# logic.net
KiCad netlist of a schematic drawn in EAGLE
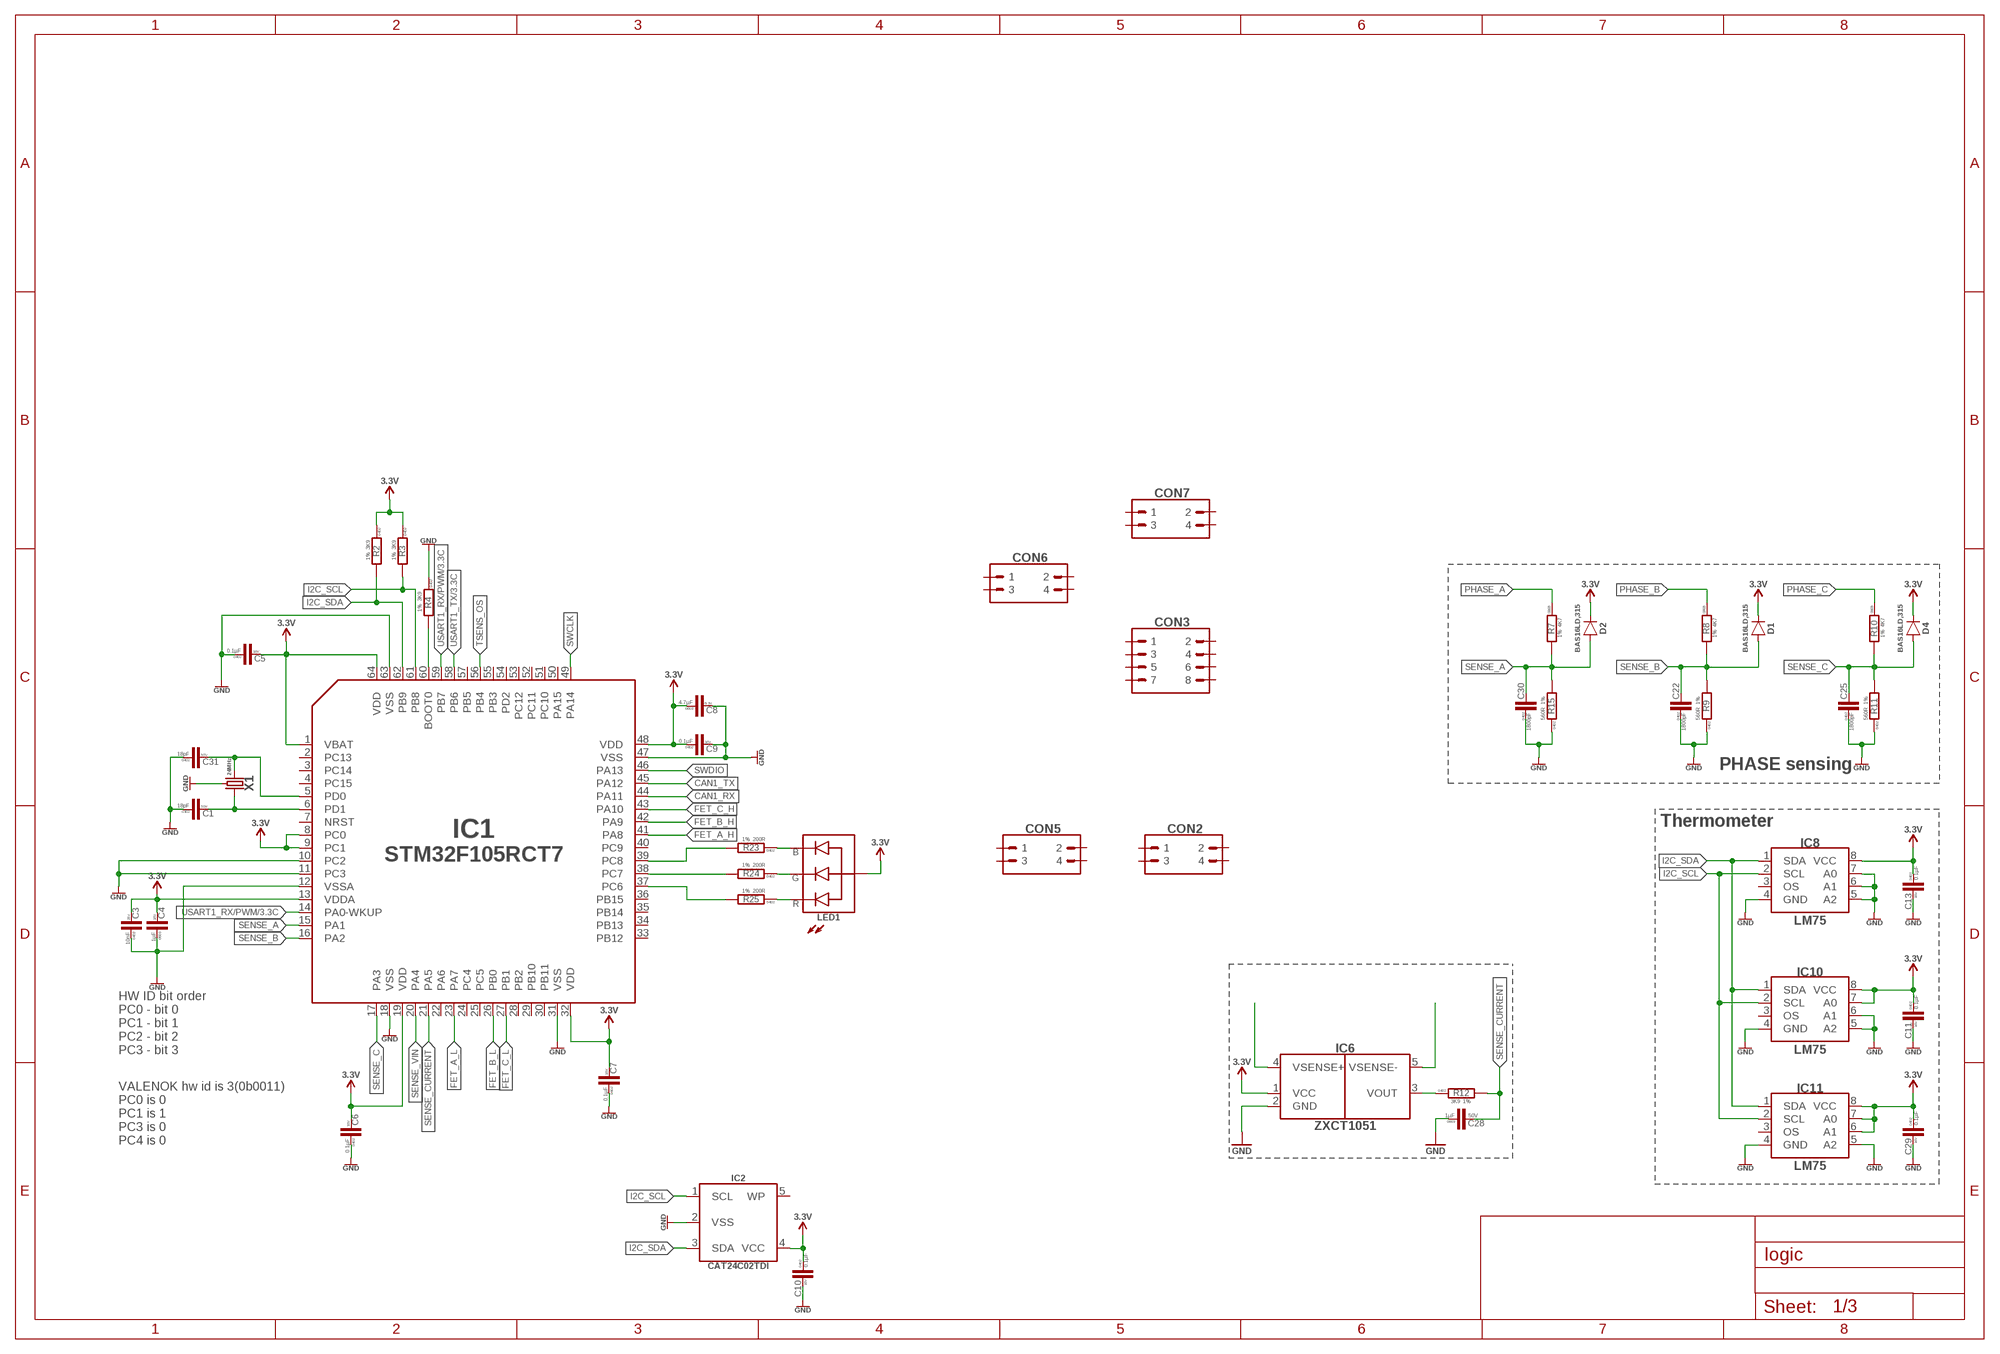
[diagram p0: schematic, sheet 1]
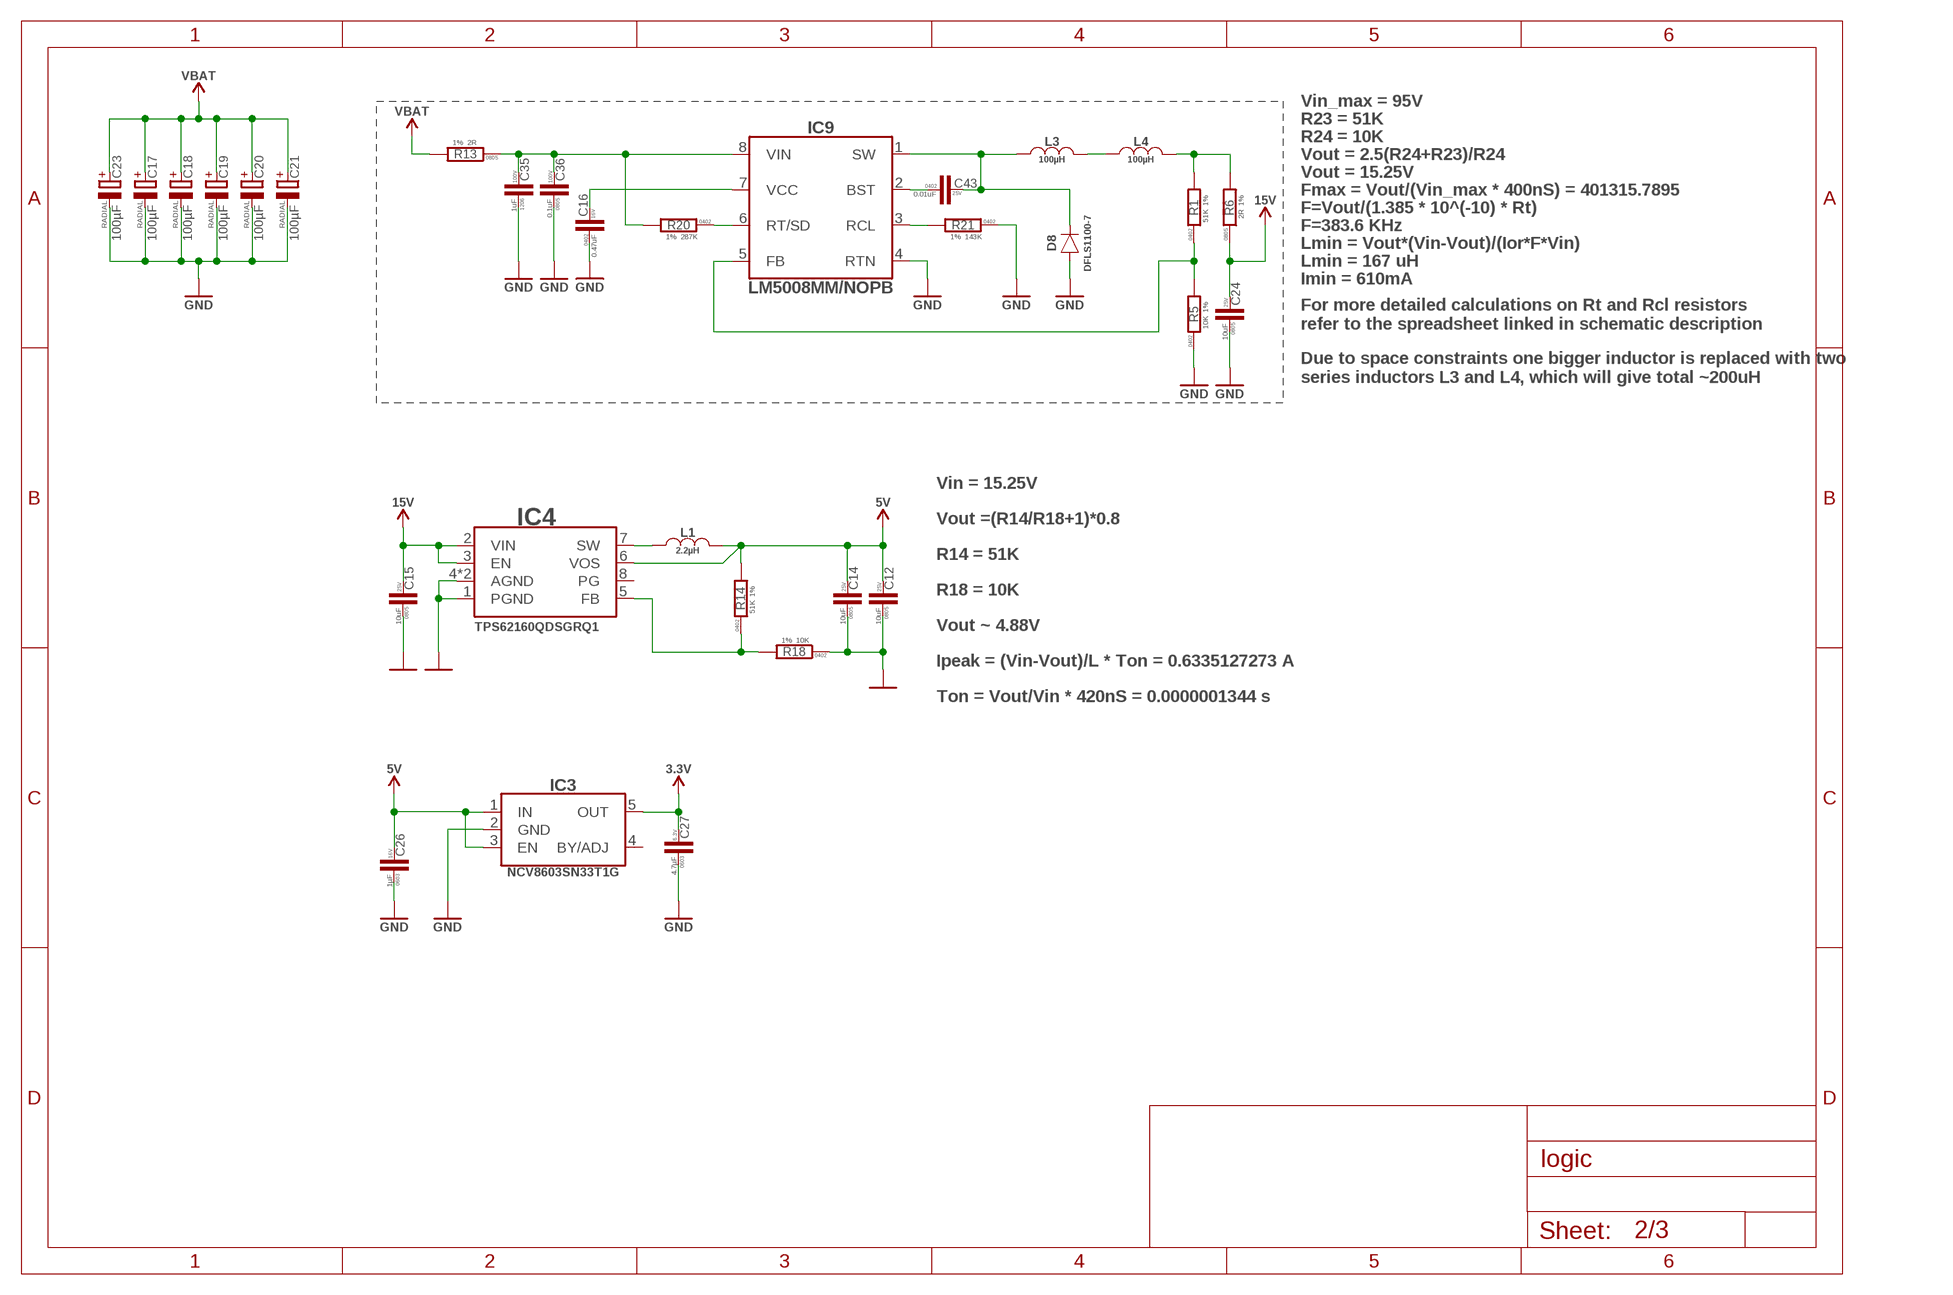
[diagram p1: schematic, sheet 2]
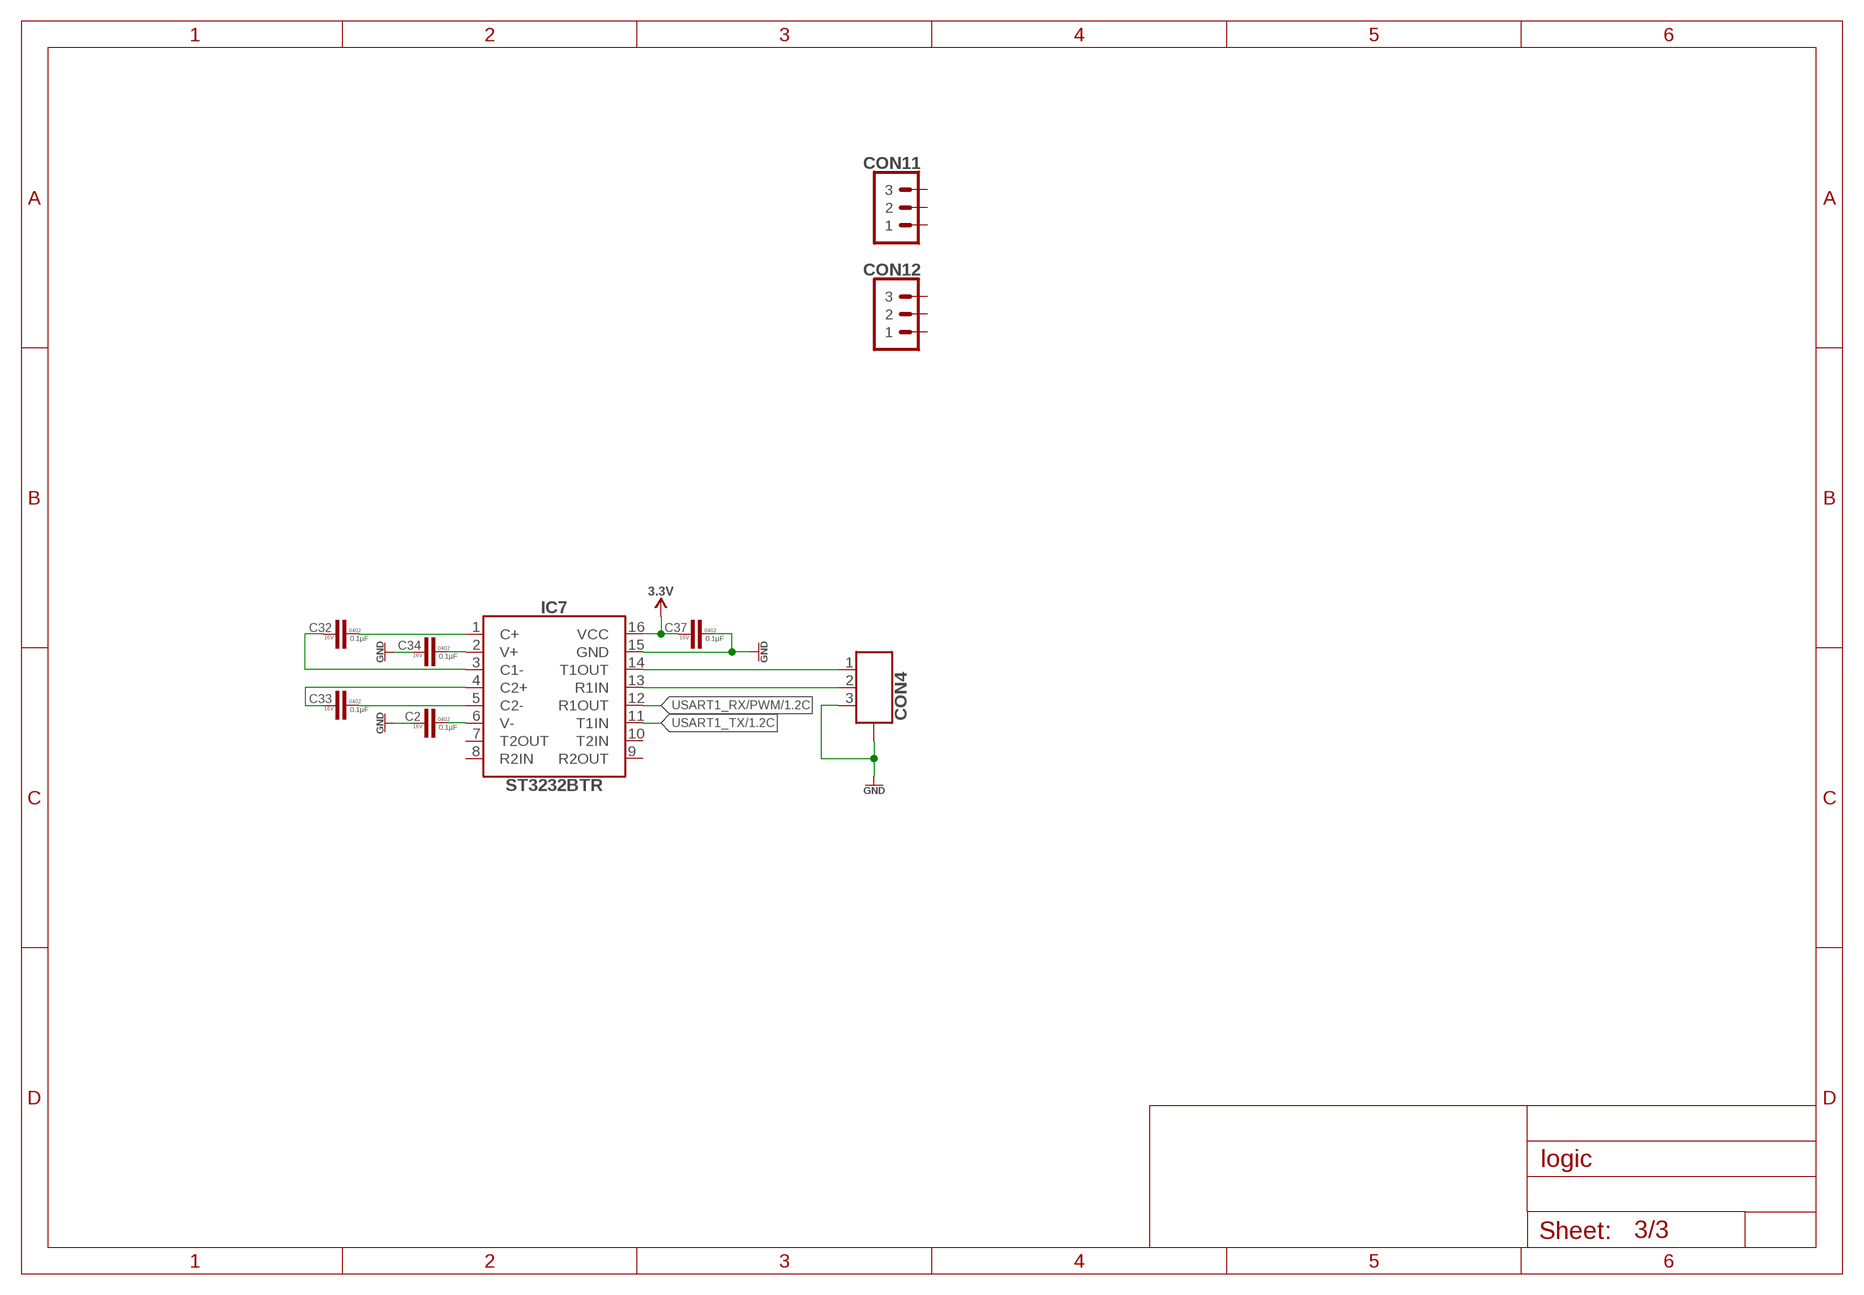
[diagram p2: schematic, sheet 3]

(export (version "E")
  (design (tool "Eeschema 10.0.6"))
  (components
    (comp (ref "C1")
      (value "18pF")
      (footprint "eagle-import:C0402")
      (fields
        (field (name "PACKAGE") "0402")
        (field (name "AEC-Q") "---")
        (field (name "DIGIKEY#") "399-8828-1-ND")
        (field (name "MANF") "Kemet")
        (field (name "MANF#") "CBR04C180F5GAC")
        (field (name "OPERATING_TEMP") "-55°C ~ 125°C")
        (field (name "VOLTAGE") "50V")
      )
      (libsource (lib "eagle-import") (part "C-0402"))
    )
    (comp (ref "C3")
      (value "10nF")
      (footprint "eagle-import:C0402")
      (fields
        (field (name "PACKAGE") "0402")
        (field (name "AEC-Q") "---")
        (field (name "DIGIKEY#") "490-6043-1-ND")
        (field (name "MANF") "Murata Electronics")
        (field (name "MANF#") "GCM155R71E103KA37D")
        (field (name "OPERATING_TEMP") "-55°C ~ 125°C")
        (field (name "VOLTAGE") "25V")
      )
      (libsource (lib "eagle-import") (part "C-0402"))
    )
    (comp (ref "C4")
      (value "1µF")
      (footprint "eagle-import:C0603")
      (fields
        (field (name "PACKAGE") "0603")
        (field (name "AEC-Q") "AEC-Q200")
        (field (name "DIGIKEY#") "445-12539-1-ND")
        (field (name "MANF") "TDK Corporation")
        (field (name "MANF#") "CGA3E1X7R1C105K080AC")
        (field (name "OPERATING_TEMP") "-55°C ~ 125°C")
        (field (name "VOLTAGE") "16V")
      )
      (libsource (lib "eagle-import") (part "C-0603"))
    )
    (comp (ref "C5")
      (value "0.1µF")
      (footprint "eagle-import:C0402")
      (fields
        (field (name "PACKAGE") "0402")
        (field (name "AEC-Q") "---")
        (field (name "DIGIKEY#") "490-3261-1-ND")
        (field (name "MANF") "Murata Electronics")
        (field (name "MANF#") "GRM155R71C104KA88D")
        (field (name "OPERATING_TEMP") "-55°C ~ 125°C")
        (field (name "VOLTAGE") "16V")
      )
      (libsource (lib "eagle-import") (part "C-0402"))
    )
    (comp (ref "C6")
      (value "0.1µF")
      (footprint "eagle-import:C0402")
      (fields
        (field (name "PACKAGE") "0402")
        (field (name "AEC-Q") "---")
        (field (name "DIGIKEY#") "490-3261-1-ND")
        (field (name "MANF") "Murata Electronics")
        (field (name "MANF#") "GRM155R71C104KA88D")
        (field (name "OPERATING_TEMP") "-55°C ~ 125°C")
        (field (name "VOLTAGE") "16V")
      )
      (libsource (lib "eagle-import") (part "C-0402"))
    )
    (comp (ref "C7")
      (value "0.1µF")
      (footprint "eagle-import:C0402")
      (fields
        (field (name "PACKAGE") "0402")
        (field (name "AEC-Q") "---")
        (field (name "DIGIKEY#") "490-3261-1-ND")
        (field (name "MANF") "Murata Electronics")
        (field (name "MANF#") "GRM155R71C104KA88D")
        (field (name "OPERATING_TEMP") "-55°C ~ 125°C")
        (field (name "VOLTAGE") "16V")
      )
      (libsource (lib "eagle-import") (part "C-0402"))
    )
    (comp (ref "C8")
      (value "4.7µF")
      (footprint "eagle-import:C0603")
      (fields
        (field (name "PACKAGE") "0603")
        (field (name "AEC-Q") "---")
        (field (name "MANF") "Samsung Electro-Mechanics")
        (field (name "MANF#") "CL10B475KQ8NQNC")
        (field (name "OPERATING_TEMP") "-55°C ~ 125°C")
        (field (name "VOLTAGE") "6.3V")
      )
      (libsource (lib "eagle-import") (part "C-0603"))
    )
    (comp (ref "C9")
      (value "0.1µF")
      (footprint "eagle-import:C0402")
      (fields
        (field (name "PACKAGE") "0402")
        (field (name "AEC-Q") "---")
        (field (name "DIGIKEY#") "490-3261-1-ND")
        (field (name "MANF") "Murata Electronics")
        (field (name "MANF#") "GRM155R71C104KA88D")
        (field (name "OPERATING_TEMP") "-55°C ~ 125°C")
        (field (name "VOLTAGE") "16V")
      )
      (libsource (lib "eagle-import") (part "C-0402"))
    )
    (comp (ref "C10")
      (value "0.1µF")
      (footprint "eagle-import:C0402")
      (fields
        (field (name "PACKAGE") "0402")
        (field (name "AEC-Q") "---")
        (field (name "DIGIKEY#") "490-3261-1-ND")
        (field (name "MANF") "Murata Electronics")
        (field (name "MANF#") "GRM155R71C104KA88D")
        (field (name "OPERATING_TEMP") "-55°C ~ 125°C")
        (field (name "VOLTAGE") "16V")
      )
      (libsource (lib "eagle-import") (part "C-0402"))
    )
    (comp (ref "C11")
      (value "0.1µF")
      (footprint "eagle-import:C0402")
      (fields
        (field (name "PACKAGE") "0402")
        (field (name "AEC-Q") "---")
        (field (name "DIGIKEY#") "490-3261-1-ND")
        (field (name "MANF") "Murata Electronics")
        (field (name "MANF#") "GRM155R71C104KA88D")
        (field (name "OPERATING_TEMP") "-55°C ~ 125°C")
        (field (name "VOLTAGE") "16V")
      )
      (libsource (lib "eagle-import") (part "C-0402"))
    )
    (comp (ref "C13")
      (value "0.1µF")
      (footprint "eagle-import:C0402")
      (fields
        (field (name "PACKAGE") "0402")
        (field (name "AEC-Q") "---")
        (field (name "DIGIKEY#") "490-3261-1-ND")
        (field (name "MANF") "Murata Electronics")
        (field (name "MANF#") "GRM155R71C104KA88D")
        (field (name "OPERATING_TEMP") "-55°C ~ 125°C")
        (field (name "VOLTAGE") "16V")
      )
      (libsource (lib "eagle-import") (part "C-0402"))
    )
    (comp (ref "C22")
      (value "1800pF")
      (footprint "eagle-import:C0402")
      (fields (field (name "PACKAGE") "0402"))
      (libsource (lib "eagle-import") (part "C-0402"))
    )
    (comp (ref "C25")
      (value "1800pF")
      (footprint "eagle-import:C0402")
      (fields (field (name "PACKAGE") "0402"))
      (libsource (lib "eagle-import") (part "C-0402"))
    )
    (comp (ref "C28")
      (value "1µF")
      (footprint "eagle-import:C0603")
      (fields
        (field (name "MANF") "Taiyo Yuden")
        (field (name "PACKAGE") "0603")
        (field (name "TOLERANCE") "+-10%")
        (field (name "VOLTAGE") "50V")
      )
      (libsource (lib "eagle-import") (part "1µF-0603-50V_10%_X7R"))
    )
    (comp (ref "C29")
      (value "0.1µF")
      (footprint "eagle-import:C0402")
      (fields
        (field (name "PACKAGE") "0402")
        (field (name "AEC-Q") "---")
        (field (name "DIGIKEY#") "490-3261-1-ND")
        (field (name "MANF") "Murata Electronics")
        (field (name "MANF#") "GRM155R71C104KA88D")
        (field (name "OPERATING_TEMP") "-55°C ~ 125°C")
        (field (name "VOLTAGE") "16V")
      )
      (libsource (lib "eagle-import") (part "C-0402"))
    )
    (comp (ref "C30")
      (value "1800pF")
      (footprint "eagle-import:C0402")
      (fields (field (name "PACKAGE") "0402"))
      (libsource (lib "eagle-import") (part "C-0402"))
    )
    (comp (ref "C31")
      (value "18pF")
      (footprint "eagle-import:C0402")
      (fields
        (field (name "PACKAGE") "0402")
        (field (name "AEC-Q") "---")
        (field (name "DIGIKEY#") "399-8828-1-ND")
        (field (name "MANF") "Kemet")
        (field (name "MANF#") "CBR04C180F5GAC")
        (field (name "OPERATING_TEMP") "-55°C ~ 125°C")
        (field (name "VOLTAGE") "50V")
      )
      (libsource (lib "eagle-import") (part "C-0402"))
    )
    (comp (ref "CON2")
      (value "PINHEAD_2X02-PTH-2-MALE")
      (footprint "eagle-import:2X02-PTH-2")
      (libsource (lib "eagle-import") (part "PINHEAD_2X02-PTH-2-MALE"))
    )
    (comp (ref "CON3")
      (value "PINHEAD_2X04-PLS-2")
      (footprint "eagle-import:2X04-PTH-2")
      (libsource (lib "eagle-import") (part "PINHEAD_2X04-PLS-2"))
    )
    (comp (ref "CON5")
      (value "PINHEAD_2X02-PTH-2-MALE")
      (footprint "eagle-import:2X02-PTH-2")
      (libsource (lib "eagle-import") (part "PINHEAD_2X02-PTH-2-MALE"))
    )
    (comp (ref "CON6")
      (value "PINHEAD_2X02-PTH-2-MALE")
      (footprint "eagle-import:2X02-PTH-2")
      (libsource (lib "eagle-import") (part "PINHEAD_2X02-PTH-2-MALE"))
    )
    (comp (ref "CON7")
      (value "PINHEAD_2X02-PTH-2-MALE")
      (footprint "eagle-import:2X02-PTH-2")
      (libsource (lib "eagle-import") (part "PINHEAD_2X02-PTH-2-MALE"))
    )
    (comp (ref "D1")
      (value "BAS16L")
      (footprint "eagle-import:SOD882")
      (fields (field (name "MANF#") "BAS16LD,315") (field (name "MANF") "Nexperia USA Inc"))
      (libsource (lib "eagle-import") (part "BAS16L"))
    )
    (comp (ref "D2")
      (value "BAS16L")
      (footprint "eagle-import:SOD882")
      (fields (field (name "MANF#") "BAS16LD,315") (field (name "MANF") "Nexperia USA Inc"))
      (libsource (lib "eagle-import") (part "BAS16L"))
    )
    (comp (ref "D4")
      (value "BAS16L")
      (footprint "eagle-import:SOD882")
      (fields (field (name "MANF#") "BAS16LD,315") (field (name "MANF") "Nexperia USA Inc"))
      (libsource (lib "eagle-import") (part "BAS16L"))
    )
    (comp (ref "IC1")
      (value "STM32F105RCT6")
      (footprint "eagle-import:TQFP64")
      (fields
        (field (name "MANF#") "STM32F105RCT6")
        (field (name "MANF") "STMicroelectronics")
        (field (name "DIGIKEY#") "497-11547-ND")
        (field (name "MANF#_1") "STM32F105RCT7")
      )
      (libsource (lib "eagle-import") (part "STM32F105RCT6"))
    )
    (comp (ref "IC2")
      (value "CAT24C02")
      (footprint "eagle-import:SOT23-5L@1")
      (fields (field (name "MANF") "ON Semiconductor"))
      (libsource (lib "eagle-import") (part "CAT24C02"))
    )
    (comp (ref "IC6")
      (value "ZXCT1051")
      (footprint "eagle-import:SOT23-5L")
      (fields (field (name "MANF") "Diodes Incorporated"))
      (libsource (lib "eagle-import") (part "ZXCT1051"))
    )
    (comp (ref "IC8")
      (value "LM75-TSSOP8")
      (footprint "eagle-import:TSSOP8")
      (fields (field (name "MANF") "NXP Semiconductors"))
      (libsource (lib "eagle-import") (part "LM75-TSSOP8"))
    )
    (comp (ref "IC10")
      (value "LM75-TSSOP8")
      (footprint "eagle-import:TSSOP8")
      (fields (field (name "MANF") "NXP Semiconductors"))
      (libsource (lib "eagle-import") (part "LM75-TSSOP8"))
    )
    (comp (ref "IC11")
      (value "LM75-TSSOP8")
      (footprint "eagle-import:TSSOP8")
      (fields (field (name "MANF") "NXP Semiconductors"))
      (libsource (lib "eagle-import") (part "LM75-TSSOP8"))
    )
    (comp (ref "LED1")
      (value "LTST-C19HE1WT")
      (footprint "eagle-import:0606")
      (fields (field (name "MANF") "Lite-On Inc"))
      (libsource (lib "eagle-import") (part "LTST-C19HE1WT"))
    )
    (comp (ref "R2")
      (value "3K9")
      (footprint "eagle-import:R0402")
      (fields
        (field (name "PACKAGE") "0402")
        (field (name "TOLERANCE") "1%")
        (field (name "AEC-Q") "---")
        (field (name "DIGIKEY#") "311-3.90KLRCT-ND")
        (field (name "MANF") "Yageo")
        (field (name "MANF#") "RC0402FR-073K9L")
        (field (name "OPERATING_TEMP") "-55°C ~ 155°C")
      )
      (libsource (lib "eagle-import") (part "R-0402-1%"))
    )
    (comp (ref "R3")
      (value "3K9")
      (footprint "eagle-import:R0402")
      (fields
        (field (name "PACKAGE") "0402")
        (field (name "TOLERANCE") "1%")
        (field (name "AEC-Q") "---")
        (field (name "DIGIKEY#") "311-3.90KLRCT-ND")
        (field (name "MANF") "Yageo")
        (field (name "MANF#") "RC0402FR-073K9L")
        (field (name "OPERATING_TEMP") "-55°C ~ 155°C")
      )
      (libsource (lib "eagle-import") (part "R-0402-1%"))
    )
    (comp (ref "R4")
      (value "3K9")
      (footprint "eagle-import:R0402")
      (fields
        (field (name "PACKAGE") "0402")
        (field (name "TOLERANCE") "1%")
        (field (name "AEC-Q") "---")
        (field (name "DIGIKEY#") "311-3.90KLRCT-ND")
        (field (name "MANF") "Yageo")
        (field (name "MANF#") "RC0402FR-073K9L")
        (field (name "OPERATING_TEMP") "-55°C ~ 155°C")
      )
      (libsource (lib "eagle-import") (part "R-0402-1%"))
    )
    (comp (ref "R7")
      (value "4K7")
      (footprint "eagle-import:R0805")
      (fields (field (name "PACKAGE") "0805") (field (name "TOLERANCE") "1%"))
      (libsource (lib "eagle-import") (part "R-0805-1%"))
    )
    (comp (ref "R8")
      (value "4K7")
      (footprint "eagle-import:R0805")
      (fields (field (name "PACKAGE") "0805") (field (name "TOLERANCE") "1%"))
      (libsource (lib "eagle-import") (part "R-0805-1%"))
    )
    (comp (ref "R9")
      (value "560R")
      (footprint "eagle-import:R0402")
      (fields (field (name "PACKAGE") "0402") (field (name "TOLERANCE") "1%"))
      (libsource (lib "eagle-import") (part "R-0402-1%"))
    )
    (comp (ref "R10")
      (value "4K7")
      (footprint "eagle-import:R0805")
      (fields (field (name "PACKAGE") "0805") (field (name "TOLERANCE") "1%"))
      (libsource (lib "eagle-import") (part "R-0805-1%"))
    )
    (comp (ref "R11")
      (value "560R")
      (footprint "eagle-import:R0402")
      (fields (field (name "PACKAGE") "0402") (field (name "TOLERANCE") "1%"))
      (libsource (lib "eagle-import") (part "R-0402-1%"))
    )
    (comp (ref "R12")
      (value "3K9")
      (footprint "eagle-import:R0402")
      (fields (field (name "MANF") "Yageo") (field (name "PACKAGE") "0402") (field (name "TOLERANCE") "1%"))
      (libsource (lib "eagle-import") (part "3K9-0402-1%"))
    )
    (comp (ref "R15")
      (value "560R")
      (footprint "eagle-import:R0402")
      (fields (field (name "PACKAGE") "0402") (field (name "TOLERANCE") "1%"))
      (libsource (lib "eagle-import") (part "R-0402-1%"))
    )
    (comp (ref "R23")
      (value "200R")
      (footprint "eagle-import:R0402")
      (fields
        (field (name "PACKAGE") "0402")
        (field (name "TOLERANCE") "1%")
        (field (name "AEC-Q") "---")
        (field (name "DIGIKEY#") "311-200JRCT-ND")
        (field (name "MANF") "Yageo")
        (field (name "MANF#") "RC0402JR-07200RL")
        (field (name "OPERATING_TEMP") "-55°C ~ 155°C")
      )
      (libsource (lib "eagle-import") (part "R-0402-1%"))
    )
    (comp (ref "R24")
      (value "200R")
      (footprint "eagle-import:R0402")
      (fields
        (field (name "PACKAGE") "0402")
        (field (name "TOLERANCE") "1%")
        (field (name "AEC-Q") "---")
        (field (name "DIGIKEY#") "311-200JRCT-ND")
        (field (name "MANF") "Yageo")
        (field (name "MANF#") "RC0402JR-07200RL")
        (field (name "OPERATING_TEMP") "-55°C ~ 155°C")
      )
      (libsource (lib "eagle-import") (part "R-0402-1%"))
    )
    (comp (ref "R25")
      (value "200R")
      (footprint "eagle-import:R0402")
      (fields
        (field (name "PACKAGE") "0402")
        (field (name "TOLERANCE") "1%")
        (field (name "AEC-Q") "---")
        (field (name "DIGIKEY#") "311-200JRCT-ND")
        (field (name "MANF") "Yageo")
        (field (name "MANF#") "RC0402JR-07200RL")
        (field (name "OPERATING_TEMP") "-55°C ~ 155°C")
      )
      (libsource (lib "eagle-import") (part "R-0402-1%"))
    )
    (comp (ref "X1")
      (value "24MHz")
      (footprint "eagle-import:OSCILLATOR-3.2X2.5-4P")
      (fields
        (field (name "MANF") "Kyocera International Inc. Electronic Components")
        (field (name "DIGIKEY#") "1253-1198-1-ND")
        (field (name "MANF#") "CX3225GB24000P0HPQCC")
      )
      (libsource (lib "eagle-import") (part "CRYSTAL-4P-3.2X2.5-4P-24MHZ"))
    )
    (comp (ref "C12")
      (value "10uF")
      (footprint "eagle-import:C0805")
      (fields
        (field (name "PACKAGE") "0805")
        (field (name "AEC-Q") "AEC-Q200")
        (field (name "DIGIKEY#") "445-181411-1-ND")
        (field (name "MANF") "TDK Corporation")
        (field (name "MANF#") "CGA4J1X7S1E106K125AE")
        (field (name "VOLTAGE") "25V")
      )
      (libsource (lib "eagle-import") (part "C-0805"))
    )
    (comp (ref "C14")
      (value "10uF")
      (footprint "eagle-import:C0805")
      (fields
        (field (name "PACKAGE") "0805")
        (field (name "AEC-Q") "AEC-Q200")
        (field (name "DIGIKEY#") "445-181411-1-ND")
        (field (name "MANF") "TDK Corporation")
        (field (name "MANF#") "CGA4J1X7S1E106K125AE")
        (field (name "VOLTAGE") "25V")
      )
      (libsource (lib "eagle-import") (part "C-0805"))
    )
    (comp (ref "C15")
      (value "10uF")
      (footprint "eagle-import:C0805")
      (fields
        (field (name "PACKAGE") "0805")
        (field (name "AEC-Q") "AEC-Q200")
        (field (name "DIGIKEY#") "445-181411-1-ND")
        (field (name "MANF") "TDK Corporation")
        (field (name "MANF#") "CGA4J1X7S1E106K125AE")
        (field (name "VOLTAGE") "25V")
      )
      (libsource (lib "eagle-import") (part "C-0805"))
    )
    (comp (ref "C16")
      (value "0.47uF")
      (footprint "eagle-import:C0402")
      (fields
        (field (name "PACKAGE") "0402")
        (field (name "AEC-Q") "AEC-Q200")
        (field (name "DIGIKEY#") "490-12244-1-ND")
        (field (name "MANF") "Murata Electronics")
        (field (name "MANF#") "GRT155C81C474ME01D")
        (field (name "VOLTAGE") "16V")
      )
      (libsource (lib "eagle-import") (part "C-0402"))
    )
    (comp (ref "C17")
      (value "100µF")
      (footprint "eagle-import:RADIAL_SIDE_12.5X22")
      (fields
        (field (name "PACKAGE") "RADIAL")
        (field (name "MANF") "EPCOS (TDK)")
        (field (name "VOLTAGE") "50V")
        (field (name "DIGIKEY#") "493-4784-3-ND")
        (field (name "MANF_1") "Nichicon")
        (field (name "MANF#") "UCY2C101MHD1TO")
        (field (name "VOLTAGE_1") "160V")
      )
      (libsource (lib "eagle-import") (part "CPOL-RADIAL_SIDE-12.5-22"))
    )
    (comp (ref "C18")
      (value "100µF")
      (footprint "eagle-import:RADIAL_SIDE_12.5X22")
      (fields
        (field (name "PACKAGE") "RADIAL")
        (field (name "MANF") "EPCOS (TDK)")
        (field (name "VOLTAGE") "50V")
        (field (name "DIGIKEY#") "493-4784-3-ND")
        (field (name "MANF_1") "Nichicon")
        (field (name "MANF#") "UCY2C101MHD1TO")
        (field (name "VOLTAGE_1") "160V")
      )
      (libsource (lib "eagle-import") (part "CPOL-RADIAL_SIDE-12.5-22"))
    )
    (comp (ref "C19")
      (value "100µF")
      (footprint "eagle-import:RADIAL_SIDE_12.5X22")
      (fields
        (field (name "PACKAGE") "RADIAL")
        (field (name "MANF") "EPCOS (TDK)")
        (field (name "VOLTAGE") "50V")
        (field (name "DIGIKEY#") "493-4784-3-ND")
        (field (name "MANF_1") "Nichicon")
        (field (name "MANF#") "UCY2C101MHD1TO")
        (field (name "VOLTAGE_1") "160V")
      )
      (libsource (lib "eagle-import") (part "CPOL-RADIAL_SIDE-12.5-22"))
    )
    (comp (ref "C20")
      (value "100µF")
      (footprint "eagle-import:RADIAL_SIDE_12.5X22")
      (fields
        (field (name "PACKAGE") "RADIAL")
        (field (name "MANF") "EPCOS (TDK)")
        (field (name "VOLTAGE") "50V")
        (field (name "DIGIKEY#") "493-4784-3-ND")
        (field (name "MANF_1") "Nichicon")
        (field (name "MANF#") "UCY2C101MHD1TO")
        (field (name "VOLTAGE_1") "160V")
      )
      (libsource (lib "eagle-import") (part "CPOL-RADIAL_SIDE-12.5-22"))
    )
    (comp (ref "C21")
      (value "100µF")
      (footprint "eagle-import:RADIAL_SIDE_12.5X22")
      (fields
        (field (name "PACKAGE") "RADIAL")
        (field (name "MANF") "EPCOS (TDK)")
        (field (name "VOLTAGE") "50V")
        (field (name "DIGIKEY#") "493-4784-3-ND")
        (field (name "MANF_1") "Nichicon")
        (field (name "MANF#") "UCY2C101MHD1TO")
        (field (name "VOLTAGE_1") "160V")
      )
      (libsource (lib "eagle-import") (part "CPOL-RADIAL_SIDE-12.5-22"))
    )
    (comp (ref "C23")
      (value "100µF")
      (footprint "eagle-import:RADIAL_SIDE_12.5X22")
      (fields
        (field (name "PACKAGE") "RADIAL")
        (field (name "MANF") "EPCOS (TDK)")
        (field (name "VOLTAGE") "50V")
        (field (name "DIGIKEY#") "493-4784-3-ND")
        (field (name "MANF_1") "Nichicon")
        (field (name "MANF#") "UCY2C101MHD1TO")
        (field (name "VOLTAGE_1") "160V")
      )
      (libsource (lib "eagle-import") (part "CPOL-RADIAL_SIDE-12.5-22"))
    )
    (comp (ref "C24")
      (value "10uF")
      (footprint "eagle-import:C0805")
      (fields
        (field (name "PACKAGE") "0805")
        (field (name "AEC-Q") "AEC-Q200")
        (field (name "DIGIKEY#") "445-181411-1-ND")
        (field (name "MANF") "TDK Corporation")
        (field (name "MANF#") "CGA4J1X7S1E106K125AE")
        (field (name "VOLTAGE") "25V")
      )
      (libsource (lib "eagle-import") (part "C-0805"))
    )
    (comp (ref "C26")
      (value "1µF")
      (footprint "eagle-import:C0603")
      (fields
        (field (name "PACKAGE") "0603")
        (field (name "AEC-Q") "AEC-Q200")
        (field (name "DIGIKEY#") "445-12539-1-ND")
        (field (name "MANF") "TDK Corporation")
        (field (name "MANF#") "CGA3E1X7R1C105K080AC")
        (field (name "OPERATING_TEMP") "-55°C ~ 125°C")
        (field (name "VOLTAGE") "16V")
      )
      (libsource (lib "eagle-import") (part "C-0603"))
    )
    (comp (ref "C27")
      (value "4.7µF")
      (footprint "eagle-import:C0603")
      (fields
        (field (name "PACKAGE") "0603")
        (field (name "AEC-Q") "---")
        (field (name "DIGIKEY#") "1276-2087-1-ND")
        (field (name "MANF") "Samsung Electro-Mechanics")
        (field (name "MANF#") "CL10B475KQ8NQNC")
        (field (name "OPERATING_TEMP") "-55°C ~ 125°C")
        (field (name "VOLTAGE") "6.3V")
      )
      (libsource (lib "eagle-import") (part "C-0603"))
    )
    (comp (ref "C35")
      (value "1uF")
      (footprint "eagle-import:C1206")
      (fields
        (field (name "PACKAGE") "1206")
        (field (name "AEC-Q") "AEC-Q200")
        (field (name "DIGIKEY#") "490-16468-1-ND")
        (field (name "MANF") "Murata Electronics")
        (field (name "MANF#") "GCJ31CR72A105KA01L")
        (field (name "VOLTAGE") "100V")
      )
      (libsource (lib "eagle-import") (part "C-1206"))
    )
    (comp (ref "C36")
      (value "0.1uF")
      (footprint "eagle-import:C0805")
      (fields
        (field (name "PACKAGE") "0805")
        (field (name "AEC-Q") "AEC-Q200")
        (field (name "DIGIKEY#") "445-5827-1-ND")
        (field (name "MANF") "TDK Corporation")
        (field (name "MANF#") "CGA4J2X7R2A104K125AA")
        (field (name "VOLTAGE") "100V")
      )
      (libsource (lib "eagle-import") (part "C-0805"))
    )
    (comp (ref "C43")
      (value "0.01uF")
      (footprint "eagle-import:C0402")
      (fields
        (field (name "PACKAGE") "0402")
        (field (name "DIGIKEY#") "490-6043-1-ND")
        (field (name "MANF") "Murata Electronics")
        (field (name "MANF#") "GCM155R71E103KA37D")
        (field (name "VOLTAGE") "25V")
      )
      (libsource (lib "eagle-import") (part "C-0402"))
    )
    (comp (ref "D8")
      (value "DFLS1100")
      (footprint "eagle-import:POWERDI-123")
      (fields (field (name "MANF#") "DFLS1100-7") (field (name "MANF") "Diodes Incorporated"))
      (libsource (lib "eagle-import") (part "DFLS1100"))
    )
    (comp (ref "IC3")
      (value "NCV8603SN33")
      (footprint "eagle-import:SOT23-5")
      (fields (field (name "MANF") "ON Semiconductor") (field (name "MANF#") "NCV8603SN33T1G"))
      (libsource (lib "eagle-import") (part "NCV8603SN33"))
    )
    (comp (ref "IC4")
      (value "TPS62160QDSGRQ1")
      (footprint "eagle-import:WFDFN-8")
      (fields
        (field (name "MANF#") "TPS62160DSGR")
        (field (name "MANF") "Texas Instruments")
        (field (name "AEC-Q") "AEC-Q100")
        (field (name "DIGIKEY#") "296-40840-1-ND")
        (field (name "MANF#_1") "TPS62160QDSGRQ1")
      )
      (libsource (lib "eagle-import") (part "TPS62160QDSGRQ1"))
    )
    (comp (ref "IC9")
      (value "LM5008-MSOP8")
      (footprint "eagle-import:MSOP8")
      (fields (field (name "MANF#") "LM5008MM/NOPB") (field (name "MANF") "Texas Instruments"))
      (libsource (lib "eagle-import") (part "LM5008-MSOP8"))
    )
    (comp (ref "L1")
      (value "2.2µH")
      (footprint "eagle-import:NR3015")
      (fields (field (name "MANF") "Taiyo Yuden"))
      (libsource (lib "eagle-import") (part "2.2µH-NRS3015"))
    )
    (comp (ref "L3")
      (value "100µH")
      (footprint "eagle-import:LQS-6028")
      (fields (field (name "MANF") "Wurth Electronics Inc"))
      (libsource (lib "eagle-import") (part "100µH-LQS-6028"))
    )
    (comp (ref "L4")
      (value "100µH")
      (footprint "eagle-import:LQS-6028")
      (fields (field (name "MANF") "Wurth Electronics Inc"))
      (libsource (lib "eagle-import") (part "100µH-LQS-6028"))
    )
    (comp (ref "R1")
      (value "51K")
      (footprint "eagle-import:R0402")
      (fields
        (field (name "PACKAGE") "0402")
        (field (name "TOLERANCE") "1%")
        (field (name "AEC-Q") "AEC-Q200")
        (field (name "DIGIKEY#") "P51.0KLCT-ND")
        (field (name "MANF") "Panasonic Electronic Components")
        (field (name "MANF#") "ERJ-2RKF5102X")
      )
      (libsource (lib "eagle-import") (part "R-0402-1%"))
    )
    (comp (ref "R5")
      (value "10K")
      (footprint "eagle-import:R0402")
      (fields
        (field (name "PACKAGE") "0402")
        (field (name "TOLERANCE") "1%")
        (field (name "AEC-Q") "AEC-Q200")
        (field (name "DIGIKEY#") "P10.0KLCT-ND")
        (field (name "MANF") "Panasonic Electronic Components")
        (field (name "MANF#") "ERJ-2RKF1002X")
      )
      (libsource (lib "eagle-import") (part "R-0402-1%"))
    )
    (comp (ref "R6")
      (value "2R")
      (footprint "eagle-import:R0805")
      (fields
        (field (name "PACKAGE") "0805")
        (field (name "TOLERANCE") "1%")
        (field (name "DIGIKEY#") "RMCF0805FT2R00CT-ND")
        (field (name "MANF") "Stackpole Electronics Inc")
        (field (name "MANF#") "RMCF0805FT2R00")
      )
      (libsource (lib "eagle-import") (part "R-0805-1%"))
    )
    (comp (ref "R13")
      (value "2R")
      (footprint "eagle-import:R0805")
      (fields
        (field (name "PACKAGE") "0805")
        (field (name "TOLERANCE") "1%")
        (field (name "DIGIKEY#") "RMCF0805FT2R00CT-ND")
        (field (name "MANF") "Stackpole Electronics Inc")
        (field (name "MANF#") "RMCF0805FT2R00")
      )
      (libsource (lib "eagle-import") (part "R-0805-1%"))
    )
    (comp (ref "R14")
      (value "51K")
      (footprint "eagle-import:R0402")
      (fields
        (field (name "PACKAGE") "0402")
        (field (name "TOLERANCE") "1%")
        (field (name "AEC-Q") "AEC-Q200")
        (field (name "DIGIKEY#") "P51.0KLCT-ND")
        (field (name "MANF") "Panasonic Electronic Components")
        (field (name "MANF#") "ERJ-2RKF5102X")
      )
      (libsource (lib "eagle-import") (part "R-0402-1%"))
    )
    (comp (ref "R18")
      (value "10K")
      (footprint "eagle-import:R0402")
      (fields
        (field (name "PACKAGE") "0402")
        (field (name "TOLERANCE") "1%")
        (field (name "AEC-Q") "AEC-Q200")
        (field (name "DIGIKEY#") "P10.0KLCT-ND")
        (field (name "MANF") "Panasonic Electronic Components")
        (field (name "MANF#") "ERJ-2RKF1002X")
      )
      (libsource (lib "eagle-import") (part "R-0402-1%"))
    )
    (comp (ref "R20")
      (value "287K")
      (footprint "eagle-import:R0402")
      (fields
        (field (name "PACKAGE") "0402")
        (field (name "TOLERANCE") "1%")
        (field (name "AEC-Q") "AEC-Q200")
        (field (name "DIGIKEY#") "P287KLCT-ND")
        (field (name "MANF") "Panasonic Electronic Components")
        (field (name "MANF#") "ERJ-2RKF2873X")
      )
      (libsource (lib "eagle-import") (part "R-0402-1%"))
    )
    (comp (ref "R21")
      (value "143K")
      (footprint "eagle-import:R0402")
      (fields
        (field (name "PACKAGE") "0402")
        (field (name "TOLERANCE") "1%")
        (field (name "AEC-Q") "AEC-Q200")
        (field (name "DIGIKEY#") "P122734CT-ND")
        (field (name "MANF") "Panasonic Electronic Components")
        (field (name "MANF#") "ERJ-1GNF1433C")
      )
      (libsource (lib "eagle-import") (part "R-0402-1%"))
    )
    (comp (ref "C2")
      (value "0.1µF")
      (footprint "eagle-import:C0402")
      (fields
        (field (name "PACKAGE") "0402")
        (field (name "AEC-Q") "---")
        (field (name "DIGIKEY#") "490-3261-1-ND")
        (field (name "MANF") "Murata Electronics")
        (field (name "MANF#") "GRM155R71C104KA88D")
        (field (name "OPERATING_TEMP") "-55°C ~ 125°C")
        (field (name "VOLTAGE") "16V")
      )
      (libsource (lib "eagle-import") (part "C-0402"))
    )
    (comp (ref "C32")
      (value "0.1µF")
      (footprint "eagle-import:C0402")
      (fields
        (field (name "PACKAGE") "0402")
        (field (name "AEC-Q") "---")
        (field (name "DIGIKEY#") "490-3261-1-ND")
        (field (name "MANF") "Murata Electronics")
        (field (name "MANF#") "GRM155R71C104KA88D")
        (field (name "OPERATING_TEMP") "-55°C ~ 125°C")
        (field (name "VOLTAGE") "16V")
      )
      (libsource (lib "eagle-import") (part "C-0402"))
    )
    (comp (ref "C33")
      (value "0.1µF")
      (footprint "eagle-import:C0402")
      (fields
        (field (name "PACKAGE") "0402")
        (field (name "AEC-Q") "---")
        (field (name "DIGIKEY#") "490-3261-1-ND")
        (field (name "MANF") "Murata Electronics")
        (field (name "MANF#") "GRM155R71C104KA88D")
        (field (name "OPERATING_TEMP") "-55°C ~ 125°C")
        (field (name "VOLTAGE") "16V")
      )
      (libsource (lib "eagle-import") (part "C-0402"))
    )
    (comp (ref "C34")
      (value "0.1µF")
      (footprint "eagle-import:C0402")
      (fields
        (field (name "PACKAGE") "0402")
        (field (name "AEC-Q") "---")
        (field (name "DIGIKEY#") "490-3261-1-ND")
        (field (name "MANF") "Murata Electronics")
        (field (name "MANF#") "GRM155R71C104KA88D")
        (field (name "OPERATING_TEMP") "-55°C ~ 125°C")
        (field (name "VOLTAGE") "16V")
      )
      (libsource (lib "eagle-import") (part "C-0402"))
    )
    (comp (ref "C37")
      (value "0.1µF")
      (footprint "eagle-import:C0402")
      (fields
        (field (name "PACKAGE") "0402")
        (field (name "AEC-Q") "---")
        (field (name "DIGIKEY#") "490-3261-1-ND")
        (field (name "MANF") "Murata Electronics")
        (field (name "MANF#") "GRM155R71C104KA88D")
        (field (name "OPERATING_TEMP") "-55°C ~ 125°C")
        (field (name "VOLTAGE") "16V")
      )
      (libsource (lib "eagle-import") (part "C-0402"))
    )
    (comp (ref "CON4")
      (value "CON-3P-TABS")
      (footprint "eagle-import:JST_GH-3P-RA")
      (libsource (lib "eagle-import") (part "CON-3P-TABS"))
    )
    (comp (ref "CON11")
      (value "PINHEAD_1X03-2")
      (footprint "eagle-import:1X03-PTH-2")
      (libsource (lib "eagle-import") (part "PINHEAD_1X03-2"))
    )
    (comp (ref "CON12")
      (value "PINHEAD_1X03-2")
      (footprint "eagle-import:1X03-PTH-2")
      (libsource (lib "eagle-import") (part "PINHEAD_1X03-2"))
    )
    (comp (ref "IC7")
      (value "ST3232")
      (footprint "eagle-import:TSSOP16")
      (fields (field (name "MANF#") "ST3232BTR") (field (name "MANF") "STMicroelectronics"))
      (libsource (lib "eagle-import") (part "ST3232"))
    )
  )
  (nets
    (net (code "1") (name "CAN1_RX") (class "Default")
      (node (ref "IC1") (pin "44") (pinfunction "PA11_44") (pintype "bidirectional"))
    )
    (net (code "2") (name "CAN1_TX") (class "Default")
      (node (ref "IC1") (pin "45") (pinfunction "PA12_45") (pintype "bidirectional"))
    )
    (net (code "3") (name "FET_A_H") (class "Default")
      (node (ref "IC1") (pin "41") (pinfunction "PA8_41") (pintype "bidirectional"))
    )
    (net (code "4") (name "FET_A_L") (class "Default")
      (node (ref "IC1") (pin "23") (pinfunction "PA7_23") (pintype "bidirectional"))
    )
    (net (code "5") (name "FET_B_H") (class "Default")
      (node (ref "IC1") (pin "42") (pinfunction "PA9_42") (pintype "bidirectional"))
    )
    (net (code "6") (name "FET_B_L") (class "Default")
      (node (ref "IC1") (pin "26") (pinfunction "PB0_26") (pintype "bidirectional"))
    )
    (net (code "7") (name "FET_C_H") (class "Default")
      (node (ref "IC1") (pin "43") (pinfunction "PA10_43") (pintype "bidirectional"))
    )
    (net (code "8") (name "FET_C_L") (class "Default")
      (node (ref "IC1") (pin "27") (pinfunction "PB1_27") (pintype "bidirectional"))
    )
    (net (code "9") (name "GND") (class "Default")
      (node (ref "C1") (pin "1") (pinfunction "1_1") (pintype "passive"))
      (node (ref "C10") (pin "2") (pinfunction "2_2") (pintype "passive"))
      (node (ref "C11") (pin "2") (pinfunction "2_2") (pintype "passive"))
      (node (ref "C12") (pin "1") (pinfunction "1_1") (pintype "passive"))
      (node (ref "C13") (pin "2") (pinfunction "2_2") (pintype "passive"))
      (node (ref "C14") (pin "1") (pinfunction "1_1") (pintype "passive"))
      (node (ref "C15") (pin "1") (pinfunction "1_1") (pintype "passive"))
      (node (ref "C16") (pin "1") (pinfunction "1_1") (pintype "passive"))
      (node (ref "C17") (pin "-") (pinfunction "-_-") (pintype "passive"))
      (node (ref "C18") (pin "-") (pinfunction "-_-") (pintype "passive"))
      (node (ref "C19") (pin "-") (pinfunction "-_-") (pintype "passive"))
      (node (ref "C2") (pin "2") (pinfunction "2_2") (pintype "passive"))
      (node (ref "C20") (pin "-") (pinfunction "-_-") (pintype "passive"))
      (node (ref "C21") (pin "-") (pinfunction "-_-") (pintype "passive"))
      (node (ref "C22") (pin "1") (pinfunction "1_1") (pintype "passive"))
      (node (ref "C23") (pin "-") (pinfunction "-_-") (pintype "passive"))
      (node (ref "C24") (pin "1") (pinfunction "1_1") (pintype "passive"))
      (node (ref "C25") (pin "1") (pinfunction "1_1") (pintype "passive"))
      (node (ref "C26") (pin "1") (pinfunction "1_1") (pintype "passive"))
      (node (ref "C27") (pin "1") (pinfunction "1_1") (pintype "passive"))
      (node (ref "C28") (pin "P$1") (pinfunction "1_P$1") (pintype "passive"))
      (node (ref "C29") (pin "2") (pinfunction "2_2") (pintype "passive"))
      (node (ref "C3") (pin "1") (pinfunction "1_1") (pintype "passive"))
      (node (ref "C30") (pin "1") (pinfunction "1_1") (pintype "passive"))
      (node (ref "C31") (pin "1") (pinfunction "1_1") (pintype "passive"))
      (node (ref "C34") (pin "2") (pinfunction "2_2") (pintype "passive"))
      (node (ref "C35") (pin "P$1") (pinfunction "1_P$1") (pintype "passive"))
      (node (ref "C36") (pin "1") (pinfunction "1_1") (pintype "passive"))
      (node (ref "C37") (pin "1") (pinfunction "1_1") (pintype "passive"))
      (node (ref "C4") (pin "1") (pinfunction "1_1") (pintype "passive"))
      (node (ref "C5") (pin "1") (pinfunction "1_1") (pintype "passive"))
      (node (ref "C6") (pin "1") (pinfunction "1_1") (pintype "passive"))
      (node (ref "C7") (pin "1") (pinfunction "1_1") (pintype "passive"))
      (node (ref "C8") (pin "2") (pinfunction "2_2") (pintype "passive"))
      (node (ref "C9") (pin "2") (pinfunction "2_2") (pintype "passive"))
      (node (ref "CON4") (pin "3") (pinfunction "3_3") (pintype "bidirectional"))
      (node (ref "CON4") (pin "M$0") (pinfunction "GND_M$0") (pintype "bidirectional"))
      (node (ref "CON4") (pin "M$1") (pinfunction "GND_M$1") (pintype "bidirectional"))
      (node (ref "D8") (pin "A") (pinfunction "A_A") (pintype "passive"))
      (node (ref "IC1") (pin "10") (pinfunction "PC2_10") (pintype "bidirectional"))
      (node (ref "IC1") (pin "11") (pinfunction "PC3_11") (pintype "bidirectional"))
      (node (ref "IC1") (pin "12") (pinfunction "VSSA_12") (pintype "bidirectional"))
      (node (ref "IC1") (pin "18") (pinfunction "VSS_18") (pintype "bidirectional"))
      (node (ref "IC1") (pin "31") (pinfunction "VSS_31") (pintype "bidirectional"))
      (node (ref "IC1") (pin "47") (pinfunction "VSS_47") (pintype "bidirectional"))
      (node (ref "IC1") (pin "63") (pinfunction "VSS_63") (pintype "bidirectional"))
      (node (ref "IC10") (pin "4") (pinfunction "GND_4") (pintype "bidirectional"))
      (node (ref "IC10") (pin "5") (pinfunction "A2_5") (pintype "bidirectional"))
      (node (ref "IC10") (pin "6") (pinfunction "A1_6") (pintype "bidirectional"))
      (node (ref "IC11") (pin "4") (pinfunction "GND_4") (pintype "bidirectional"))
      (node (ref "IC11") (pin "5") (pinfunction "A2_5") (pintype "bidirectional"))
      (node (ref "IC2") (pin "2") (pinfunction "VSS_2") (pintype "bidirectional"))
      (node (ref "IC3") (pin "2") (pinfunction "GND_2") (pintype "power_in"))
      (node (ref "IC4") (pin "1") (pinfunction "PGND_1") (pintype "bidirectional"))
      (node (ref "IC4") (pin "4") (pinfunction "AGND_4") (pintype "bidirectional"))
      (node (ref "IC4") (pin "EP") (pinfunction "AGND_EP") (pintype "bidirectional"))
      (node (ref "IC6") (pin "2") (pinfunction "GND_2") (pintype "bidirectional"))
      (node (ref "IC7") (pin "15") (pinfunction "GND_15") (pintype "bidirectional"))
      (node (ref "IC8") (pin "4") (pinfunction "GND_4") (pintype "bidirectional"))
      (node (ref "IC8") (pin "5") (pinfunction "A2_5") (pintype "bidirectional"))
      (node (ref "IC8") (pin "6") (pinfunction "A1_6") (pintype "bidirectional"))
      (node (ref "IC8") (pin "7") (pinfunction "A0_7") (pintype "bidirectional"))
      (node (ref "IC9") (pin "4") (pinfunction "RTN_4") (pintype "bidirectional"))
      (node (ref "R11") (pin "1") (pinfunction "1_1") (pintype "passive"))
      (node (ref "R15") (pin "1") (pinfunction "1_1") (pintype "passive"))
      (node (ref "R18") (pin "1") (pinfunction "1_1") (pintype "passive"))
      (node (ref "R21") (pin "1") (pinfunction "1_1") (pintype "passive"))
      (node (ref "R4") (pin "1") (pinfunction "1_1") (pintype "passive"))
      (node (ref "R5") (pin "1") (pinfunction "1_1") (pintype "passive"))
      (node (ref "R9") (pin "1") (pinfunction "1_1") (pintype "passive"))
      (node (ref "X1") (pin "2") (pinfunction "GND_2") (pintype "bidirectional"))
      (node (ref "X1") (pin "4") (pinfunction "GND_4") (pintype "bidirectional"))
    )
    (net (code "10") (name "I2C_SCL") (class "Default")
      (node (ref "IC1") (pin "61") (pinfunction "PB8_61") (pintype "bidirectional"))
      (node (ref "IC10") (pin "2") (pinfunction "SCL_2") (pintype "bidirectional"))
      (node (ref "IC11") (pin "2") (pinfunction "SCL_2") (pintype "bidirectional"))
      (node (ref "IC2") (pin "1") (pinfunction "SCL_1") (pintype "bidirectional"))
      (node (ref "IC8") (pin "2") (pinfunction "SCL_2") (pintype "bidirectional"))
      (node (ref "R3") (pin "2") (pinfunction "2_2") (pintype "passive"))
    )
    (net (code "11") (name "I2C_SDA") (class "Default")
      (node (ref "IC1") (pin "62") (pinfunction "PB9_62") (pintype "bidirectional"))
      (node (ref "IC10") (pin "1") (pinfunction "SDA_1") (pintype "bidirectional"))
      (node (ref "IC11") (pin "1") (pinfunction "SDA_1") (pintype "bidirectional"))
      (node (ref "IC2") (pin "3") (pinfunction "SDA_3") (pintype "bidirectional"))
      (node (ref "IC8") (pin "1") (pinfunction "SDA_1") (pintype "bidirectional"))
      (node (ref "R2") (pin "2") (pinfunction "2_2") (pintype "passive"))
    )
    (net (code "12") (name "Net-(C35-2)") (class "Default")
      (node (ref "C35") (pin "P$2") (pinfunction "2_P$2") (pintype "passive"))
      (node (ref "C36") (pin "2") (pinfunction "2_2") (pintype "passive"))
      (node (ref "IC9") (pin "8") (pinfunction "VIN_8") (pintype "bidirectional"))
      (node (ref "R13") (pin "1") (pinfunction "1_1") (pintype "passive"))
      (node (ref "R20") (pin "2") (pinfunction "2_2") (pintype "passive"))
    )
    (net (code "13") (name "Net-(IC1-BOOT0)") (class "Default")
      (node (ref "IC1") (pin "60") (pinfunction "BOOT0_60") (pintype "bidirectional"))
      (node (ref "R4") (pin "2") (pinfunction "2_2") (pintype "passive"))
    )
    (net (code "14") (name "Net-(IC1-PC6)") (class "Default")
      (node (ref "IC1") (pin "37") (pinfunction "PC6_37") (pintype "bidirectional"))
      (node (ref "R25") (pin "2") (pinfunction "2_2") (pintype "passive"))
    )
    (net (code "15") (name "Net-(IC1-PC7)") (class "Default")
      (node (ref "IC1") (pin "38") (pinfunction "PC7_38") (pintype "bidirectional"))
      (node (ref "R24") (pin "2") (pinfunction "2_2") (pintype "passive"))
    )
    (net (code "16") (name "Net-(IC1-PC8)") (class "Default")
      (node (ref "IC1") (pin "39") (pinfunction "PC8_39") (pintype "bidirectional"))
      (node (ref "R23") (pin "2") (pinfunction "2_2") (pintype "passive"))
    )
    (net (code "17") (name "Net-(IC1-PD0)") (class "Default")
      (node (ref "C31") (pin "2") (pinfunction "2_2") (pintype "passive"))
      (node (ref "IC1") (pin "5") (pinfunction "PD0_5") (pintype "bidirectional"))
      (node (ref "X1") (pin "3") (pinfunction "2_3") (pintype "passive"))
    )
    (net (code "18") (name "Net-(IC1-PD1)") (class "Default")
      (node (ref "C1") (pin "2") (pinfunction "2_2") (pintype "passive"))
      (node (ref "IC1") (pin "6") (pinfunction "PD1_6") (pintype "bidirectional"))
      (node (ref "X1") (pin "1") (pinfunction "1_1") (pintype "passive"))
    )
    (net (code "19") (name "Net-(IC4-FB)") (class "Default")
      (node (ref "IC4") (pin "5") (pinfunction "FB_5") (pintype "bidirectional"))
      (node (ref "R14") (pin "1") (pinfunction "1_1") (pintype "passive"))
      (node (ref "R18") (pin "2") (pinfunction "2_2") (pintype "passive"))
    )
    (net (code "20") (name "Net-(IC4-SW)") (class "Default")
      (node (ref "IC4") (pin "7") (pinfunction "SW_7") (pintype "bidirectional"))
      (node (ref "L1") (pin "1") (pinfunction "1_1") (pintype "bidirectional"))
    )
    (net (code "21") (name "Net-(IC6-VOUT)") (class "Default")
      (node (ref "IC6") (pin "3") (pinfunction "VOUT_3") (pintype "bidirectional"))
      (node (ref "R12") (pin "1") (pinfunction "1_1") (pintype "passive"))
    )
    (net (code "22") (name "Net-(IC7-C+)") (class "Default")
      (node (ref "C32") (pin "1") (pinfunction "1_1") (pintype "passive"))
      (node (ref "IC7") (pin "1") (pinfunction "C+_1") (pintype "bidirectional"))
    )
    (net (code "23") (name "Net-(IC7-C1-)") (class "Default")
      (node (ref "C32") (pin "2") (pinfunction "2_2") (pintype "passive"))
      (node (ref "IC7") (pin "3") (pinfunction "C1-_3") (pintype "bidirectional"))
    )
    (net (code "24") (name "Net-(IC7-C2+)") (class "Default")
      (node (ref "C33") (pin "2") (pinfunction "2_2") (pintype "passive"))
      (node (ref "IC7") (pin "4") (pinfunction "C2+_4") (pintype "bidirectional"))
    )
    (net (code "25") (name "Net-(IC7-C2-)") (class "Default")
      (node (ref "C33") (pin "1") (pinfunction "1_1") (pintype "passive"))
      (node (ref "IC7") (pin "5") (pinfunction "C2-_5") (pintype "bidirectional"))
    )
    (net (code "26") (name "Net-(IC7-R1IN)") (class "Default")
      (node (ref "CON4") (pin "2") (pinfunction "2_2") (pintype "bidirectional"))
      (node (ref "IC7") (pin "13") (pinfunction "R1IN_13") (pintype "bidirectional"))
    )
    (net (code "27") (name "Net-(IC7-T1OUT)") (class "Default")
      (node (ref "CON4") (pin "1") (pinfunction "1_1") (pintype "bidirectional"))
      (node (ref "IC7") (pin "14") (pinfunction "T1OUT_14") (pintype "bidirectional"))
    )
    (net (code "28") (name "Net-(IC7-V+)") (class "Default")
      (node (ref "C34") (pin "1") (pinfunction "1_1") (pintype "passive"))
      (node (ref "IC7") (pin "2") (pinfunction "V+_2") (pintype "bidirectional"))
    )
    (net (code "29") (name "Net-(IC7-V-)") (class "Default")
      (node (ref "C2") (pin "1") (pinfunction "1_1") (pintype "passive"))
      (node (ref "IC7") (pin "6") (pinfunction "V-_6") (pintype "bidirectional"))
    )
    (net (code "30") (name "Net-(IC9-BST)") (class "Default")
      (node (ref "C43") (pin "1") (pinfunction "1_1") (pintype "passive"))
      (node (ref "IC9") (pin "2") (pinfunction "BST_2") (pintype "bidirectional"))
    )
    (net (code "31") (name "Net-(IC9-FB)") (class "Default")
      (node (ref "IC9") (pin "5") (pinfunction "FB_5") (pintype "bidirectional"))
      (node (ref "R1") (pin "1") (pinfunction "1_1") (pintype "passive"))
      (node (ref "R5") (pin "2") (pinfunction "2_2") (pintype "passive"))
    )
    (net (code "32") (name "Net-(IC9-RCL)") (class "Default")
      (node (ref "IC9") (pin "3") (pinfunction "RCL_3") (pintype "bidirectional"))
      (node (ref "R21") (pin "2") (pinfunction "2_2") (pintype "passive"))
    )
    (net (code "33") (name "Net-(IC9-RT{slash}SD)") (class "Default")
      (node (ref "IC9") (pin "6") (pinfunction "RT/SD_6") (pintype "bidirectional"))
      (node (ref "R20") (pin "1") (pinfunction "1_1") (pintype "passive"))
    )
    (net (code "34") (name "Net-(IC9-SW)") (class "Default")
      (node (ref "C43") (pin "2") (pinfunction "2_2") (pintype "passive"))
      (node (ref "D8") (pin "C") (pinfunction "C_C") (pintype "passive"))
      (node (ref "IC9") (pin "1") (pinfunction "SW_1") (pintype "bidirectional"))
      (node (ref "L3") (pin "P$1") (pinfunction "1_P$1") (pintype "bidirectional"))
    )
    (net (code "35") (name "Net-(IC9-VCC)") (class "Default")
      (node (ref "C16") (pin "2") (pinfunction "2_2") (pintype "passive"))
      (node (ref "IC9") (pin "7") (pinfunction "VCC_7") (pintype "bidirectional"))
    )
    (net (code "36") (name "Net-(L3-2)") (class "Default")
      (node (ref "L3") (pin "P$2") (pinfunction "2_P$2") (pintype "bidirectional"))
      (node (ref "L4") (pin "P$1") (pinfunction "1_P$1") (pintype "bidirectional"))
    )
    (net (code "37") (name "Net-(L4-2)") (class "Default")
      (node (ref "L4") (pin "P$2") (pinfunction "2_P$2") (pintype "bidirectional"))
      (node (ref "R1") (pin "2") (pinfunction "2_2") (pintype "passive"))
      (node (ref "R6") (pin "2") (pinfunction "2_2") (pintype "passive"))
    )
    (net (code "38") (name "Net-(LED1-PadB)") (class "Default")
      (node (ref "LED1") (pin "B") (pinfunction "B_B") (pintype "bidirectional"))
      (node (ref "R23") (pin "1") (pinfunction "1_1") (pintype "passive"))
    )
    (net (code "39") (name "Net-(LED1-PadG)") (class "Default")
      (node (ref "LED1") (pin "G") (pinfunction "G_G") (pintype "bidirectional"))
      (node (ref "R24") (pin "1") (pinfunction "1_1") (pintype "passive"))
    )
    (net (code "40") (name "Net-(LED1-PadR)") (class "Default")
      (node (ref "LED1") (pin "R") (pinfunction "R_R") (pintype "bidirectional"))
      (node (ref "R25") (pin "1") (pinfunction "1_1") (pintype "passive"))
    )
    (net (code "41") (name "PHASE_A") (class "Default")
      (node (ref "R7") (pin "1") (pinfunction "1_1") (pintype "passive"))
    )
    (net (code "42") (name "PHASE_B") (class "Default")
      (node (ref "R8") (pin "1") (pinfunction "1_1") (pintype "passive"))
    )
    (net (code "43") (name "PHASE_C") (class "Default")
      (node (ref "R10") (pin "1") (pinfunction "1_1") (pintype "passive"))
    )
    (net (code "44") (name "SENSE_A") (class "Default")
      (node (ref "C30") (pin "2") (pinfunction "2_2") (pintype "passive"))
      (node (ref "D2") (pin "A") (pinfunction "A_A") (pintype "passive"))
      (node (ref "IC1") (pin "15") (pinfunction "PA1_15") (pintype "bidirectional"))
      (node (ref "R15") (pin "2") (pinfunction "2_2") (pintype "passive"))
      (node (ref "R7") (pin "2") (pinfunction "2_2") (pintype "passive"))
    )
    (net (code "45") (name "SENSE_B") (class "Default")
      (node (ref "C22") (pin "2") (pinfunction "2_2") (pintype "passive"))
      (node (ref "D1") (pin "A") (pinfunction "A_A") (pintype "passive"))
      (node (ref "IC1") (pin "16") (pinfunction "PA2_16") (pintype "bidirectional"))
      (node (ref "R8") (pin "2") (pinfunction "2_2") (pintype "passive"))
      (node (ref "R9") (pin "2") (pinfunction "2_2") (pintype "passive"))
    )
    (net (code "46") (name "SENSE_C") (class "Default")
      (node (ref "C25") (pin "2") (pinfunction "2_2") (pintype "passive"))
      (node (ref "D4") (pin "A") (pinfunction "A_A") (pintype "passive"))
      (node (ref "IC1") (pin "17") (pinfunction "PA3_17") (pintype "bidirectional"))
      (node (ref "R10") (pin "2") (pinfunction "2_2") (pintype "passive"))
      (node (ref "R11") (pin "2") (pinfunction "2_2") (pintype "passive"))
    )
    (net (code "47") (name "SENSE_CURRENT") (class "Default")
      (node (ref "C28") (pin "P$2") (pinfunction "2_P$2") (pintype "passive"))
      (node (ref "IC1") (pin "21") (pinfunction "PA5_21") (pintype "bidirectional"))
      (node (ref "R12") (pin "2") (pinfunction "2_2") (pintype "passive"))
    )
    (net (code "48") (name "SENSE_VIN") (class "Default")
      (node (ref "IC1") (pin "20") (pinfunction "PA4_20") (pintype "bidirectional"))
    )
    (net (code "49") (name "SWCLK") (class "Default")
      (node (ref "IC1") (pin "49") (pinfunction "PA14_49") (pintype "bidirectional"))
    )
    (net (code "50") (name "SWDIO") (class "Default")
      (node (ref "IC1") (pin "46") (pinfunction "PA13_46") (pintype "bidirectional"))
    )
    (net (code "51") (name "TSENS_OS") (class "Default")
      (node (ref "IC1") (pin "56") (pinfunction "PB4_56") (pintype "bidirectional"))
    )
    (net (code "52") (name "USART1_RX{slash}PWM") (class "Default")
      (node (ref "IC1") (pin "14") (pinfunction "PA0-WKUP_14") (pintype "bidirectional"))
      (node (ref "IC1") (pin "59") (pinfunction "PB7_59") (pintype "bidirectional"))
      (node (ref "IC7") (pin "12") (pinfunction "R1OUT_12") (pintype "bidirectional"))
    )
    (net (code "53") (name "USART1_TX") (class "Default")
      (node (ref "IC1") (pin "58") (pinfunction "PB6_58") (pintype "bidirectional"))
      (node (ref "IC7") (pin "11") (pinfunction "T1IN_11") (pintype "bidirectional"))
    )
    (net (code "54") (name "VBAT") (class "Default")
      (node (ref "C17") (pin "+") (pinfunction "+_+") (pintype "passive"))
      (node (ref "C18") (pin "+") (pinfunction "+_+") (pintype "passive"))
      (node (ref "C19") (pin "+") (pinfunction "+_+") (pintype "passive"))
      (node (ref "C20") (pin "+") (pinfunction "+_+") (pintype "passive"))
      (node (ref "C21") (pin "+") (pinfunction "+_+") (pintype "passive"))
      (node (ref "C23") (pin "+") (pinfunction "+_+") (pintype "passive"))
      (node (ref "R13") (pin "2") (pinfunction "2_2") (pintype "passive"))
    )
    (net (code "55") (name "VDD_3V3") (class "Default")
      (node (ref "C10") (pin "1") (pinfunction "1_1") (pintype "passive"))
      (node (ref "C11") (pin "1") (pinfunction "1_1") (pintype "passive"))
      (node (ref "C13") (pin "1") (pinfunction "1_1") (pintype "passive"))
      (node (ref "C27") (pin "2") (pinfunction "2_2") (pintype "passive"))
      (node (ref "C29") (pin "1") (pinfunction "1_1") (pintype "passive"))
      (node (ref "C3") (pin "2") (pinfunction "2_2") (pintype "passive"))
      (node (ref "C37") (pin "2") (pinfunction "2_2") (pintype "passive"))
      (node (ref "C4") (pin "2") (pinfunction "2_2") (pintype "passive"))
      (node (ref "C5") (pin "2") (pinfunction "2_2") (pintype "passive"))
      (node (ref "C6") (pin "2") (pinfunction "2_2") (pintype "passive"))
      (node (ref "C7") (pin "2") (pinfunction "2_2") (pintype "passive"))
      (node (ref "C8") (pin "1") (pinfunction "1_1") (pintype "passive"))
      (node (ref "C9") (pin "1") (pinfunction "1_1") (pintype "passive"))
      (node (ref "D1") (pin "C") (pinfunction "C_C") (pintype "passive"))
      (node (ref "D2") (pin "C") (pinfunction "C_C") (pintype "passive"))
      (node (ref "D4") (pin "C") (pinfunction "C_C") (pintype "passive"))
      (node (ref "IC1") (pin "1") (pinfunction "VBAT_1") (pintype "bidirectional"))
      (node (ref "IC1") (pin "13") (pinfunction "VDDA_13") (pintype "bidirectional"))
      (node (ref "IC1") (pin "19") (pinfunction "VDD_19") (pintype "bidirectional"))
      (node (ref "IC1") (pin "32") (pinfunction "VDD_32") (pintype "bidirectional"))
      (node (ref "IC1") (pin "48") (pinfunction "VDD_48") (pintype "bidirectional"))
      (node (ref "IC1") (pin "64") (pinfunction "VDD_64") (pintype "bidirectional"))
      (node (ref "IC1") (pin "8") (pinfunction "PC0_8") (pintype "bidirectional"))
      (node (ref "IC1") (pin "9") (pinfunction "PC1_9") (pintype "bidirectional"))
      (node (ref "IC10") (pin "7") (pinfunction "A0_7") (pintype "bidirectional"))
      (node (ref "IC10") (pin "8") (pinfunction "VCC_8") (pintype "bidirectional"))
      (node (ref "IC11") (pin "6") (pinfunction "A1_6") (pintype "bidirectional"))
      (node (ref "IC11") (pin "7") (pinfunction "A0_7") (pintype "bidirectional"))
      (node (ref "IC11") (pin "8") (pinfunction "VCC_8") (pintype "bidirectional"))
      (node (ref "IC2") (pin "4") (pinfunction "VCC_4") (pintype "bidirectional"))
      (node (ref "IC3") (pin "5") (pinfunction "OUT_5") (pintype "power_in"))
      (node (ref "IC6") (pin "1") (pinfunction "VCC_1") (pintype "bidirectional"))
      (node (ref "IC7") (pin "16") (pinfunction "VCC_16") (pintype "bidirectional"))
      (node (ref "IC8") (pin "8") (pinfunction "VCC_8") (pintype "bidirectional"))
      (node (ref "LED1") (pin "+") (pinfunction "A_+") (pintype "bidirectional"))
      (node (ref "R2") (pin "1") (pinfunction "1_1") (pintype "passive"))
      (node (ref "R3") (pin "1") (pinfunction "1_1") (pintype "passive"))
    )
    (net (code "56") (name "VDD_5V") (class "Default")
      (node (ref "C12") (pin "2") (pinfunction "2_2") (pintype "passive"))
      (node (ref "C14") (pin "2") (pinfunction "2_2") (pintype "passive"))
      (node (ref "C26") (pin "2") (pinfunction "2_2") (pintype "passive"))
      (node (ref "IC3") (pin "1") (pinfunction "IN_1") (pintype "power_in"))
      (node (ref "IC3") (pin "3") (pinfunction "EN_3") (pintype "input"))
      (node (ref "IC4") (pin "6") (pinfunction "VOS_6") (pintype "bidirectional"))
      (node (ref "L1") (pin "2") (pinfunction "2_2") (pintype "bidirectional"))
      (node (ref "R14") (pin "2") (pinfunction "2_2") (pintype "passive"))
    )
    (net (code "57") (name "VDD_15V") (class "Default")
      (node (ref "C15") (pin "2") (pinfunction "2_2") (pintype "passive"))
      (node (ref "C24") (pin "2") (pinfunction "2_2") (pintype "passive"))
      (node (ref "IC4") (pin "2") (pinfunction "VIN_2") (pintype "bidirectional"))
      (node (ref "IC4") (pin "3") (pinfunction "EN_3") (pintype "bidirectional"))
      (node (ref "R6") (pin "1") (pinfunction "1_1") (pintype "passive"))
    )
    (net (code "58") (name "unconnected-(CON2-Pad1)") (class "Default")
      (node (ref "CON2") (pin "1") (pinfunction "1_1") (pintype "passive"))
    )
    (net (code "59") (name "unconnected-(CON2-Pad2)") (class "Default")
      (node (ref "CON2") (pin "2") (pinfunction "2_2") (pintype "passive"))
    )
    (net (code "60") (name "unconnected-(CON2-Pad3)") (class "Default")
      (node (ref "CON2") (pin "3") (pinfunction "3_3") (pintype "passive"))
    )
    (net (code "61") (name "unconnected-(CON2-Pad4)") (class "Default")
      (node (ref "CON2") (pin "4") (pinfunction "4_4") (pintype "passive"))
    )
    (net (code "62") (name "unconnected-(CON3-Pad1)") (class "Default")
      (node (ref "CON3") (pin "1") (pinfunction "1_1") (pintype "passive"))
    )
    (net (code "63") (name "unconnected-(CON3-Pad2)") (class "Default")
      (node (ref "CON3") (pin "2") (pinfunction "2_2") (pintype "passive"))
    )
    (net (code "64") (name "unconnected-(CON3-Pad3)") (class "Default")
      (node (ref "CON3") (pin "3") (pinfunction "3_3") (pintype "passive"))
    )
    (net (code "65") (name "unconnected-(CON3-Pad4)") (class "Default")
      (node (ref "CON3") (pin "4") (pinfunction "4_4") (pintype "passive"))
    )
    (net (code "66") (name "unconnected-(CON3-Pad5)") (class "Default")
      (node (ref "CON3") (pin "5") (pinfunction "5_5") (pintype "passive"))
    )
    (net (code "67") (name "unconnected-(CON3-Pad6)") (class "Default")
      (node (ref "CON3") (pin "6") (pinfunction "6_6") (pintype "passive"))
    )
    (net (code "68") (name "unconnected-(CON3-Pad7)") (class "Default")
      (node (ref "CON3") (pin "7") (pinfunction "7_7") (pintype "passive"))
    )
    (net (code "69") (name "unconnected-(CON3-Pad8)") (class "Default")
      (node (ref "CON3") (pin "8") (pinfunction "8_8") (pintype "passive"))
    )
    (net (code "70") (name "unconnected-(CON5-Pad1)") (class "Default")
      (node (ref "CON5") (pin "1") (pinfunction "1_1") (pintype "passive"))
    )
    (net (code "71") (name "unconnected-(CON5-Pad2)") (class "Default")
      (node (ref "CON5") (pin "2") (pinfunction "2_2") (pintype "passive"))
    )
    (net (code "72") (name "unconnected-(CON5-Pad3)") (class "Default")
      (node (ref "CON5") (pin "3") (pinfunction "3_3") (pintype "passive"))
    )
    (net (code "73") (name "unconnected-(CON5-Pad4)") (class "Default")
      (node (ref "CON5") (pin "4") (pinfunction "4_4") (pintype "passive"))
    )
    (net (code "74") (name "unconnected-(CON6-Pad1)") (class "Default")
      (node (ref "CON6") (pin "1") (pinfunction "1_1") (pintype "passive"))
    )
    (net (code "75") (name "unconnected-(CON6-Pad2)") (class "Default")
      (node (ref "CON6") (pin "2") (pinfunction "2_2") (pintype "passive"))
    )
    (net (code "76") (name "unconnected-(CON6-Pad3)") (class "Default")
      (node (ref "CON6") (pin "3") (pinfunction "3_3") (pintype "passive"))
    )
    (net (code "77") (name "unconnected-(CON6-Pad4)") (class "Default")
      (node (ref "CON6") (pin "4") (pinfunction "4_4") (pintype "passive"))
    )
    (net (code "78") (name "unconnected-(CON7-Pad1)") (class "Default")
      (node (ref "CON7") (pin "1") (pinfunction "1_1") (pintype "passive"))
    )
    (net (code "79") (name "unconnected-(CON7-Pad2)") (class "Default")
      (node (ref "CON7") (pin "2") (pinfunction "2_2") (pintype "passive"))
    )
    (net (code "80") (name "unconnected-(CON7-Pad3)") (class "Default")
      (node (ref "CON7") (pin "3") (pinfunction "3_3") (pintype "passive"))
    )
    (net (code "81") (name "unconnected-(CON7-Pad4)") (class "Default")
      (node (ref "CON7") (pin "4") (pinfunction "4_4") (pintype "passive"))
    )
    (net (code "82") (name "unconnected-(CON11-Pad1)") (class "Default")
      (node (ref "CON11") (pin "1") (pinfunction "1_1") (pintype "passive"))
    )
    (net (code "83") (name "unconnected-(CON11-Pad2)") (class "Default")
      (node (ref "CON11") (pin "2") (pinfunction "2_2") (pintype "passive"))
    )
    (net (code "84") (name "unconnected-(CON11-Pad3)") (class "Default")
      (node (ref "CON11") (pin "3") (pinfunction "3_3") (pintype "passive"))
    )
    (net (code "85") (name "unconnected-(CON12-Pad1)") (class "Default")
      (node (ref "CON12") (pin "1") (pinfunction "1_1") (pintype "passive"))
    )
    (net (code "86") (name "unconnected-(CON12-Pad2)") (class "Default")
      (node (ref "CON12") (pin "2") (pinfunction "2_2") (pintype "passive"))
    )
    (net (code "87") (name "unconnected-(CON12-Pad3)") (class "Default")
      (node (ref "CON12") (pin "3") (pinfunction "3_3") (pintype "passive"))
    )
    (net (code "88") (name "unconnected-(IC1-NRST-Pad7)") (class "Default")
      (node (ref "IC1") (pin "7") (pinfunction "NRST_7") (pintype "bidirectional"))
    )
    (net (code "89") (name "unconnected-(IC1-PA6-Pad22)") (class "Default")
      (node (ref "IC1") (pin "22") (pinfunction "PA6_22") (pintype "bidirectional"))
    )
    (net (code "90") (name "unconnected-(IC1-PA15-Pad50)") (class "Default")
      (node (ref "IC1") (pin "50") (pinfunction "PA15_50") (pintype "bidirectional"))
    )
    (net (code "91") (name "unconnected-(IC1-PB2-Pad28)") (class "Default")
      (node (ref "IC1") (pin "28") (pinfunction "PB2_28") (pintype "bidirectional"))
    )
    (net (code "92") (name "unconnected-(IC1-PB3-Pad55)") (class "Default")
      (node (ref "IC1") (pin "55") (pinfunction "PB3_55") (pintype "bidirectional"))
    )
    (net (code "93") (name "unconnected-(IC1-PB5-Pad57)") (class "Default")
      (node (ref "IC1") (pin "57") (pinfunction "PB5_57") (pintype "bidirectional"))
    )
    (net (code "94") (name "unconnected-(IC1-PB10-Pad29)") (class "Default")
      (node (ref "IC1") (pin "29") (pinfunction "PB10_29") (pintype "bidirectional"))
    )
    (net (code "95") (name "unconnected-(IC1-PB11-Pad30)") (class "Default")
      (node (ref "IC1") (pin "30") (pinfunction "PB11_30") (pintype "bidirectional"))
    )
    (net (code "96") (name "unconnected-(IC1-PB12-Pad33)") (class "Default")
      (node (ref "IC1") (pin "33") (pinfunction "PB12_33") (pintype "bidirectional"))
    )
    (net (code "97") (name "unconnected-(IC1-PB13-Pad34)") (class "Default")
      (node (ref "IC1") (pin "34") (pinfunction "PB13_34") (pintype "bidirectional"))
    )
    (net (code "98") (name "unconnected-(IC1-PB14-Pad35)") (class "Default")
      (node (ref "IC1") (pin "35") (pinfunction "PB14_35") (pintype "bidirectional"))
    )
    (net (code "99") (name "unconnected-(IC1-PB15-Pad36)") (class "Default")
      (node (ref "IC1") (pin "36") (pinfunction "PB15_36") (pintype "bidirectional"))
    )
    (net (code "100") (name "unconnected-(IC1-PC4-Pad24)") (class "Default")
      (node (ref "IC1") (pin "24") (pinfunction "PC4_24") (pintype "bidirectional"))
    )
    (net (code "101") (name "unconnected-(IC1-PC5-Pad25)") (class "Default")
      (node (ref "IC1") (pin "25") (pinfunction "PC5_25") (pintype "bidirectional"))
    )
    (net (code "102") (name "unconnected-(IC1-PC9-Pad40)") (class "Default")
      (node (ref "IC1") (pin "40") (pinfunction "PC9_40") (pintype "bidirectional"))
    )
    (net (code "103") (name "unconnected-(IC1-PC10-Pad51)") (class "Default")
      (node (ref "IC1") (pin "51") (pinfunction "PC10_51") (pintype "bidirectional"))
    )
    (net (code "104") (name "unconnected-(IC1-PC11-Pad52)") (class "Default")
      (node (ref "IC1") (pin "52") (pinfunction "PC11_52") (pintype "bidirectional"))
    )
    (net (code "105") (name "unconnected-(IC1-PC12-Pad53)") (class "Default")
      (node (ref "IC1") (pin "53") (pinfunction "PC12_53") (pintype "bidirectional"))
    )
    (net (code "106") (name "unconnected-(IC1-PC13-Pad2)") (class "Default")
      (node (ref "IC1") (pin "2") (pinfunction "PC13_2") (pintype "bidirectional"))
    )
    (net (code "107") (name "unconnected-(IC1-PC14-Pad3)") (class "Default")
      (node (ref "IC1") (pin "3") (pinfunction "PC14_3") (pintype "bidirectional"))
    )
    (net (code "108") (name "unconnected-(IC1-PC15-Pad4)") (class "Default")
      (node (ref "IC1") (pin "4") (pinfunction "PC15_4") (pintype "bidirectional"))
    )
    (net (code "109") (name "unconnected-(IC1-PD2-Pad54)") (class "Default")
      (node (ref "IC1") (pin "54") (pinfunction "PD2_54") (pintype "bidirectional"))
    )
    (net (code "110") (name "unconnected-(IC2-WP-Pad5)") (class "Default")
      (node (ref "IC2") (pin "5") (pinfunction "WP_5") (pintype "bidirectional"))
    )
    (net (code "111") (name "unconnected-(IC3-BY{slash}ADJ-Pad4)") (class "Default")
      (node (ref "IC3") (pin "4") (pinfunction "BY/ADJ_4") (pintype "bidirectional"))
    )
    (net (code "112") (name "unconnected-(IC4-PG-Pad8)") (class "Default")
      (node (ref "IC4") (pin "8") (pinfunction "PG_8") (pintype "bidirectional"))
    )
    (net (code "113") (name "unconnected-(IC6-VSENSE+-Pad4)") (class "Default")
      (node (ref "IC6") (pin "4") (pinfunction "VSENSE+_4") (pintype "bidirectional"))
    )
    (net (code "114") (name "unconnected-(IC6-VSENSE--Pad5)") (class "Default")
      (node (ref "IC6") (pin "5") (pinfunction "VSENSE-_5") (pintype "bidirectional"))
    )
    (net (code "115") (name "unconnected-(IC7-R2IN-Pad8)") (class "Default")
      (node (ref "IC7") (pin "8") (pinfunction "R2IN_8") (pintype "bidirectional"))
    )
    (net (code "116") (name "unconnected-(IC7-R2OUT-Pad9)") (class "Default")
      (node (ref "IC7") (pin "9") (pinfunction "R2OUT_9") (pintype "bidirectional"))
    )
    (net (code "117") (name "unconnected-(IC7-T2IN-Pad10)") (class "Default")
      (node (ref "IC7") (pin "10") (pinfunction "T2IN_10") (pintype "bidirectional"))
    )
    (net (code "118") (name "unconnected-(IC7-T2OUT-Pad7)") (class "Default")
      (node (ref "IC7") (pin "7") (pinfunction "T2OUT_7") (pintype "bidirectional"))
    )
    (net (code "119") (name "unconnected-(IC8-OS-Pad3)") (class "Default")
      (node (ref "IC8") (pin "3") (pinfunction "OS_3") (pintype "bidirectional"))
    )
    (net (code "120") (name "unconnected-(IC10-OS-Pad3)") (class "Default")
      (node (ref "IC10") (pin "3") (pinfunction "OS_3") (pintype "bidirectional"))
    )
    (net (code "121") (name "unconnected-(IC11-OS-Pad3)") (class "Default")
      (node (ref "IC11") (pin "3") (pinfunction "OS_3") (pintype "bidirectional"))
    )
  )
)
